# Sheet_SchDoc_2022-03-31.net
KiCad netlist of a schematic drawn in Altium Designer
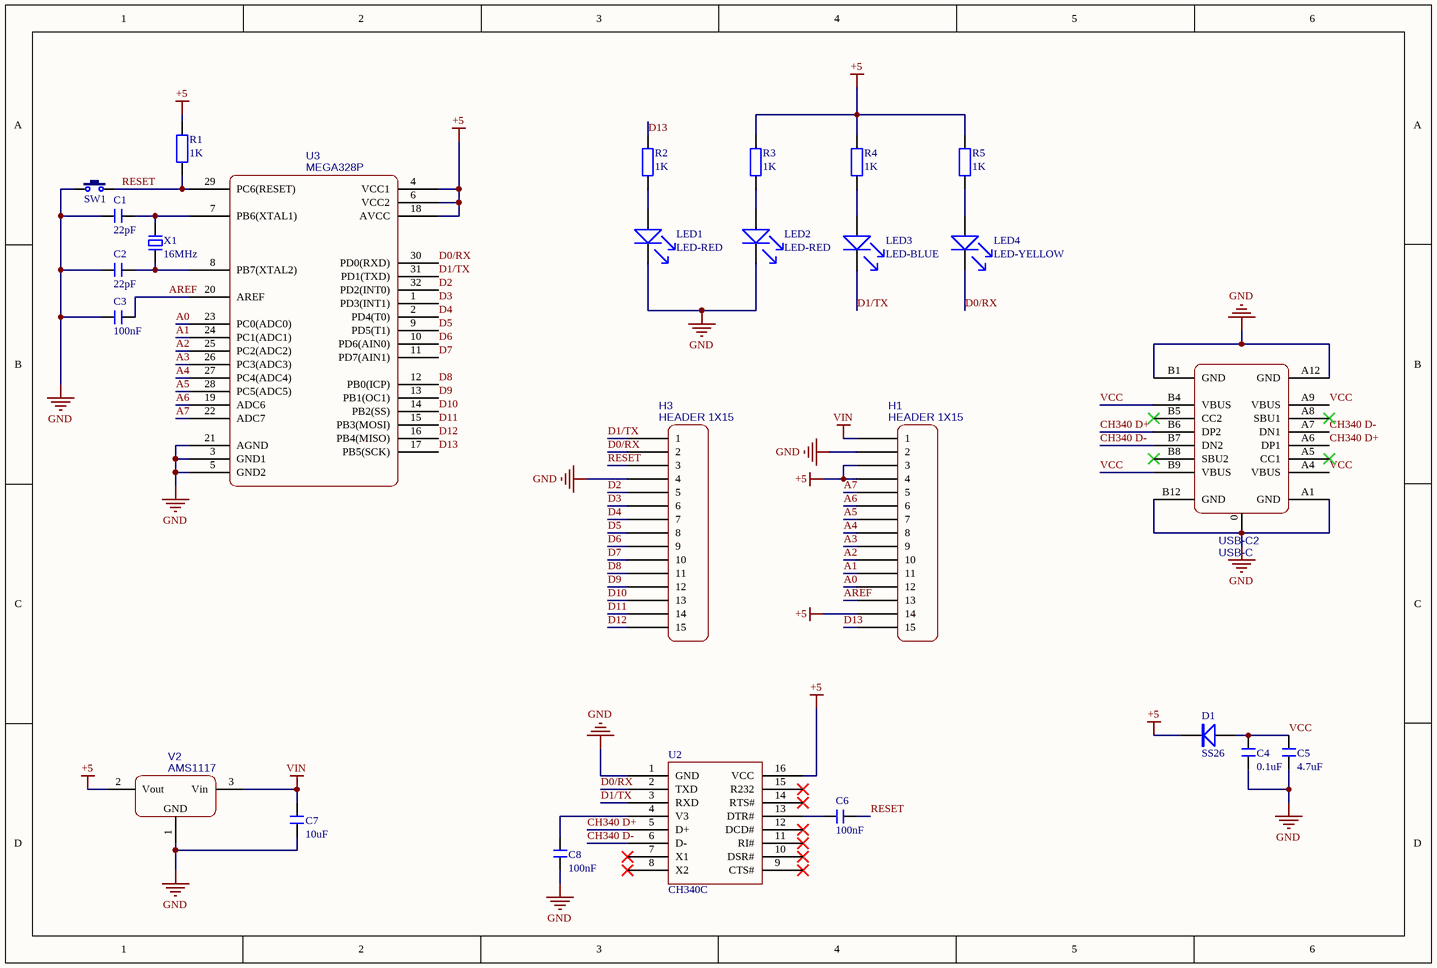
[diagram p0: Sheet.SchDoc_2022-03-31.schdoc]

(export (version "E")
  (design (tool "Eeschema 10.0.6"))
  (components
    (comp (ref "C1") (value "22pF") (libsource (lib "altium-import") (part "root_0_22pF_")))
    (comp (ref "C2") (value "22pF") (libsource (lib "altium-import") (part "root_0_22pF_")))
    (comp (ref "C3") (value "100nF") (libsource (lib "altium-import") (part "root_0_100nF_")))
    (comp (ref "C4") (value "0.1uF") (libsource (lib "altium-import") (part "root_1_0.1uF_")))
    (comp (ref "C5") (value "4.7uF") (libsource (lib "altium-import") (part "root_1_4.7uF_")))
    (comp (ref "C6") (value "100nF") (libsource (lib "") (part "root_0_100nF__1")))
    (comp (ref "C7") (value "10uF") (libsource (lib "altium-import") (part "root_1_10uF_")))
    (comp (ref "C8") (value "100nF") (libsource (lib "altium-import") (part "root_1_100nF_")))
    (comp (ref "D1") (value "SS26") (libsource (lib "altium-import") (part "root_2_SS26_")))
    (comp (ref "H1")
      (value "HEADER 1X15")
      (fields (field (name "CONTRIBUTOR") "Aknice"))
      (libsource (lib "altium-import") (part "root_0_HEADER 1X15_"))
    )
    (comp (ref "H3")
      (value "HEADER 1X15")
      (fields (field (name "CONTRIBUTOR") "Aknice"))
      (libsource (lib "altium-import") (part "root_0_HEADER 1X15_"))
    )
    (comp (ref "LED1") (value "LED-RED") (libsource (lib "altium-import") (part "root_3_LED-RED_")))
    (comp (ref "LED2") (value "LED-RED") (libsource (lib "altium-import") (part "root_3_LED-RED_")))
    (comp (ref "LED3") (value "LED-BLUE") (libsource (lib "altium-import") (part "root_3_LED-BLUE_")))
    (comp (ref "LED4") (value "LED-YELLOW") (libsource (lib "altium-import") (part "root_3_LED-YELLOW_")))
    (comp (ref "R1") (value "1K") (libsource (lib "altium-import") (part "root_1_1K_")))
    (comp (ref "R2") (value "1K") (libsource (lib "altium-import") (part "root_1_1K_")))
    (comp (ref "R3") (value "1K") (libsource (lib "altium-import") (part "root_1_1K_")))
    (comp (ref "R4") (value "1K") (libsource (lib "altium-import") (part "root_1_1K_")))
    (comp (ref "R5") (value "1K") (libsource (lib "altium-import") (part "root_1_1K_")))
    (comp (ref "SW1") (value "3x6x5") (libsource (lib "altium-import") (part "root_0_3x6x5_")))
    (comp (ref "U2") (value "CH340C") (libsource (lib "altium-import") (part "root_0_CH340C_")))
    (comp (ref "U3")
      (value "MEGA328P")
      (fields (field (name "CONTRIBUTOR") "Aknice"))
      (libsource (lib "altium-import") (part "root_0_MEGA328P_"))
    )
    (comp (ref "USB-C2")
      (value "USB-C")
      (fields (field (name "CONTRIBUTOR") "Aknice"))
      (libsource (lib "altium-import") (part "root_0_USB-C_"))
    )
    (comp (ref "V2")
      (value "AMS1117")
      (fields (field (name "CONTRIBUTOR") "Aknice"))
      (libsource (lib "altium-import") (part "root_0_AMS1117_"))
    )
    (comp (ref "X1") (value "16MHz") (libsource (lib "altium-import") (part "root_1_16MHz_")))
  )
  (nets
    (net (code "1") (name "+5") (class "Default")
      (node (ref "D1") (pin "2") (pinfunction "K_2") (pintype "passive"))
      (node (ref "H1") (pin "14") (pinfunction "14_14") (pintype "passive"))
      (node (ref "H1") (pin "3") (pinfunction "3_3") (pintype "passive"))
      (node (ref "H1") (pin "4") (pinfunction "4_4") (pintype "passive"))
      (node (ref "R1") (pin "2") (pinfunction "2_2") (pintype "passive"))
      (node (ref "R3") (pin "2") (pinfunction "2_2") (pintype "passive"))
      (node (ref "R4") (pin "2") (pinfunction "2_2") (pintype "passive"))
      (node (ref "R5") (pin "2") (pinfunction "2_2") (pintype "passive"))
      (node (ref "U2") (pin "16") (pinfunction "VCC_16") (pintype "passive"))
      (node (ref "U3") (pin "18") (pinfunction "AVCC_18") (pintype "passive"))
      (node (ref "U3") (pin "4") (pinfunction "VCC1_4") (pintype "passive"))
      (node (ref "U3") (pin "6") (pinfunction "VCC2_6") (pintype "passive"))
      (node (ref "V2") (pin "2") (pinfunction "Vout_2") (pintype "passive"))
    )
    (net (code "2") (name "/A0") (class "Default")
      (node (ref "H1") (pin "12") (pinfunction "12_12") (pintype "passive"))
      (node (ref "U3") (pin "23") (pinfunction "PC0(ADC0)_23") (pintype "passive"))
    )
    (net (code "3") (name "/A1") (class "Default")
      (node (ref "H1") (pin "11") (pinfunction "11_11") (pintype "passive"))
      (node (ref "U3") (pin "24") (pinfunction "PC1(ADC1)_24") (pintype "passive"))
    )
    (net (code "4") (name "/A2") (class "Default")
      (node (ref "H1") (pin "10") (pinfunction "10_10") (pintype "passive"))
      (node (ref "U3") (pin "25") (pinfunction "PC2(ADC2)_25") (pintype "passive"))
    )
    (net (code "5") (name "/A3") (class "Default")
      (node (ref "H1") (pin "9") (pinfunction "9_9") (pintype "passive"))
      (node (ref "U3") (pin "26") (pinfunction "PC3(ADC3)_26") (pintype "passive"))
    )
    (net (code "6") (name "/A4") (class "Default")
      (node (ref "H1") (pin "8") (pinfunction "8_8") (pintype "passive"))
      (node (ref "U3") (pin "27") (pinfunction "PC4(ADC4)_27") (pintype "passive"))
    )
    (net (code "7") (name "/A5") (class "Default")
      (node (ref "H1") (pin "7") (pinfunction "7_7") (pintype "passive"))
      (node (ref "U3") (pin "28") (pinfunction "PC5(ADC5)_28") (pintype "passive"))
    )
    (net (code "8") (name "/A6") (class "Default")
      (node (ref "H1") (pin "6") (pinfunction "6_6") (pintype "passive"))
      (node (ref "U3") (pin "19") (pinfunction "ADC6_19") (pintype "passive"))
    )
    (net (code "9") (name "/A7") (class "Default")
      (node (ref "H1") (pin "5") (pinfunction "5_5") (pintype "passive"))
      (node (ref "U3") (pin "22") (pinfunction "ADC7_22") (pintype "passive"))
    )
    (net (code "10") (name "/AREF") (class "Default")
      (node (ref "C3") (pin "2") (pinfunction "2_2") (pintype "passive"))
      (node (ref "H1") (pin "13") (pinfunction "13_13") (pintype "passive"))
      (node (ref "U3") (pin "20") (pinfunction "AREF_20") (pintype "passive"))
    )
    (net (code "11") (name "/CH340 D+") (class "Default")
      (node (ref "U2") (pin "5") (pinfunction "D+_5") (pintype "passive"))
      (node (ref "USB-C2") (pin "A6") (pinfunction "DP1_A6") (pintype "passive"))
      (node (ref "USB-C2") (pin "B6") (pinfunction "DP2_B6") (pintype "passive"))
    )
    (net (code "12") (name "/CH340 D-") (class "Default")
      (node (ref "U2") (pin "6") (pinfunction "D-_6") (pintype "passive"))
      (node (ref "USB-C2") (pin "A7") (pinfunction "DN1_A7") (pintype "passive"))
      (node (ref "USB-C2") (pin "B7") (pinfunction "DN2_B7") (pintype "passive"))
    )
    (net (code "13") (name "/D0{slash}RX") (class "Default")
      (node (ref "H3") (pin "2") (pinfunction "2_2") (pintype "passive"))
      (node (ref "LED4") (pin "2") (pinfunction "2_2") (pintype "passive"))
      (node (ref "U2") (pin "2") (pinfunction "TXD_2") (pintype "passive"))
      (node (ref "U3") (pin "30") (pinfunction "PD0(RXD)_30") (pintype "passive"))
    )
    (net (code "14") (name "/D1{slash}TX") (class "Default")
      (node (ref "H3") (pin "1") (pinfunction "1_1") (pintype "passive"))
      (node (ref "LED3") (pin "2") (pinfunction "2_2") (pintype "passive"))
      (node (ref "U2") (pin "3") (pinfunction "RXD_3") (pintype "passive"))
      (node (ref "U3") (pin "31") (pinfunction "PD1(TXD)_31") (pintype "passive"))
    )
    (net (code "15") (name "/D2") (class "Default")
      (node (ref "H3") (pin "5") (pinfunction "5_5") (pintype "passive"))
      (node (ref "U3") (pin "32") (pinfunction "PD2(INT0)_32") (pintype "passive"))
    )
    (net (code "16") (name "/D3") (class "Default")
      (node (ref "H3") (pin "6") (pinfunction "6_6") (pintype "passive"))
      (node (ref "U3") (pin "1") (pinfunction "PD3(INT1)_1") (pintype "passive"))
    )
    (net (code "17") (name "/D4") (class "Default")
      (node (ref "H3") (pin "7") (pinfunction "7_7") (pintype "passive"))
      (node (ref "U3") (pin "2") (pinfunction "PD4(T0)_2") (pintype "passive"))
    )
    (net (code "18") (name "/D5") (class "Default")
      (node (ref "H3") (pin "8") (pinfunction "8_8") (pintype "passive"))
      (node (ref "U3") (pin "9") (pinfunction "PD5(T1)_9") (pintype "passive"))
    )
    (net (code "19") (name "/D6") (class "Default")
      (node (ref "H3") (pin "9") (pinfunction "9_9") (pintype "passive"))
      (node (ref "U3") (pin "10") (pinfunction "PD6(AIN0)_10") (pintype "passive"))
    )
    (net (code "20") (name "/D7") (class "Default")
      (node (ref "H3") (pin "10") (pinfunction "10_10") (pintype "passive"))
      (node (ref "U3") (pin "11") (pinfunction "PD7(AIN1)_11") (pintype "passive"))
    )
    (net (code "21") (name "/D8") (class "Default")
      (node (ref "H3") (pin "11") (pinfunction "11_11") (pintype "passive"))
      (node (ref "U3") (pin "12") (pinfunction "PB0(ICP)_12") (pintype "passive"))
    )
    (net (code "22") (name "/D9") (class "Default")
      (node (ref "H3") (pin "12") (pinfunction "12_12") (pintype "passive"))
      (node (ref "U3") (pin "13") (pinfunction "PB1(OC1)_13") (pintype "passive"))
    )
    (net (code "23") (name "/D10") (class "Default")
      (node (ref "H3") (pin "13") (pinfunction "13_13") (pintype "passive"))
      (node (ref "U3") (pin "14") (pinfunction "PB2(SS)_14") (pintype "passive"))
    )
    (net (code "24") (name "/D11") (class "Default")
      (node (ref "H3") (pin "14") (pinfunction "14_14") (pintype "passive"))
      (node (ref "U3") (pin "15") (pinfunction "PB3(MOSI)_15") (pintype "passive"))
    )
    (net (code "25") (name "/D12") (class "Default")
      (node (ref "H3") (pin "15") (pinfunction "15_15") (pintype "passive"))
      (node (ref "U3") (pin "16") (pinfunction "PB4(MISO)_16") (pintype "passive"))
    )
    (net (code "26") (name "/D13") (class "Default")
      (node (ref "H1") (pin "15") (pinfunction "15_15") (pintype "passive"))
      (node (ref "R2") (pin "2") (pinfunction "2_2") (pintype "passive"))
      (node (ref "U3") (pin "17") (pinfunction "PB5(SCK)_17") (pintype "passive"))
    )
    (net (code "27") (name "/RESET") (class "Default")
      (node (ref "C6") (pin "1") (pinfunction "1_1") (pintype "passive"))
      (node (ref "H3") (pin "3") (pinfunction "3_3") (pintype "passive"))
      (node (ref "R1") (pin "1") (pinfunction "1_1") (pintype "passive"))
      (node (ref "SW1") (pin "2") (pinfunction "2_2") (pintype "passive"))
      (node (ref "U3") (pin "29") (pinfunction "PC6(RESET)_29") (pintype "passive"))
    )
    (net (code "28") (name "/VCC") (class "Default")
      (node (ref "C4") (pin "2") (pinfunction "2_2") (pintype "passive"))
      (node (ref "C5") (pin "2") (pinfunction "2_2") (pintype "passive"))
      (node (ref "D1") (pin "1") (pinfunction "A_1") (pintype "passive"))
      (node (ref "USB-C2") (pin "A4") (pinfunction "VBUS_A4") (pintype "passive"))
      (node (ref "USB-C2") (pin "A9") (pinfunction "VBUS_A9") (pintype "passive"))
      (node (ref "USB-C2") (pin "B4") (pinfunction "VBUS_B4") (pintype "passive"))
      (node (ref "USB-C2") (pin "B9") (pinfunction "VBUS_B9") (pintype "passive"))
    )
    (net (code "29") (name "GND") (class "Default")
      (node (ref "C1") (pin "1") (pinfunction "1_1") (pintype "passive"))
      (node (ref "C2") (pin "1") (pinfunction "1_1") (pintype "passive"))
      (node (ref "C3") (pin "1") (pinfunction "1_1") (pintype "passive"))
      (node (ref "C4") (pin "1") (pinfunction "1_1") (pintype "passive"))
      (node (ref "C5") (pin "1") (pinfunction "1_1") (pintype "passive"))
      (node (ref "C7") (pin "1") (pinfunction "1_1") (pintype "passive"))
      (node (ref "C8") (pin "1") (pinfunction "1_1") (pintype "passive"))
      (node (ref "H1") (pin "2") (pinfunction "2_2") (pintype "passive"))
      (node (ref "H3") (pin "4") (pinfunction "4_4") (pintype "passive"))
      (node (ref "LED1") (pin "2") (pinfunction "2_2") (pintype "passive"))
      (node (ref "LED2") (pin "2") (pinfunction "2_2") (pintype "passive"))
      (node (ref "SW1") (pin "1") (pinfunction "1_1") (pintype "passive"))
      (node (ref "U2") (pin "1") (pinfunction "GND_1") (pintype "passive"))
      (node (ref "U3") (pin "21") (pinfunction "AGND_21") (pintype "passive"))
      (node (ref "U3") (pin "3") (pinfunction "GND1_3") (pintype "passive"))
      (node (ref "U3") (pin "5") (pinfunction "GND2_5") (pintype "passive"))
      (node (ref "USB-C2") (pin "A1") (pinfunction "GND_A1") (pintype "passive"))
      (node (ref "USB-C2") (pin "A12") (pinfunction "GND_A12") (pintype "passive"))
      (node (ref "USB-C2") (pin "B1") (pinfunction "GND_B1") (pintype "passive"))
      (node (ref "USB-C2") (pin "B12") (pinfunction "GND_B12") (pintype "passive"))
      (node (ref "V2") (pin "1") (pinfunction "GND_1") (pintype "passive"))
    )
    (net (code "30") (name "Net-(LED1-Pad1)") (class "Default")
      (node (ref "LED1") (pin "1") (pinfunction "1_1") (pintype "passive"))
      (node (ref "R2") (pin "1") (pinfunction "1_1") (pintype "passive"))
    )
    (net (code "31") (name "Net-(LED2-Pad1)") (class "Default")
      (node (ref "LED2") (pin "1") (pinfunction "1_1") (pintype "passive"))
      (node (ref "R3") (pin "1") (pinfunction "1_1") (pintype "passive"))
    )
    (net (code "32") (name "Net-(LED3-Pad1)") (class "Default")
      (node (ref "LED3") (pin "1") (pinfunction "1_1") (pintype "passive"))
      (node (ref "R4") (pin "1") (pinfunction "1_1") (pintype "passive"))
    )
    (net (code "33") (name "Net-(LED4-Pad1)") (class "Default")
      (node (ref "LED4") (pin "1") (pinfunction "1_1") (pintype "passive"))
      (node (ref "R5") (pin "1") (pinfunction "1_1") (pintype "passive"))
    )
    (net (code "34") (name "Net-(U2-DTR#)") (class "Default")
      (node (ref "C6") (pin "2") (pinfunction "2_2") (pintype "passive"))
      (node (ref "U2") (pin "13") (pinfunction "DTR#_13") (pintype "passive"))
    )
    (net (code "35") (name "Net-(U2-V3)") (class "Default")
      (node (ref "C8") (pin "2") (pinfunction "2_2") (pintype "passive"))
      (node (ref "U2") (pin "4") (pinfunction "V3_4") (pintype "passive"))
    )
    (net (code "36") (name "Net-(U3-PB6(XTAL1))") (class "Default")
      (node (ref "C1") (pin "2") (pinfunction "2_2") (pintype "passive"))
      (node (ref "U3") (pin "7") (pinfunction "PB6(XTAL1)_7") (pintype "passive"))
      (node (ref "X1") (pin "2") (pinfunction "2_2") (pintype "passive"))
    )
    (net (code "37") (name "Net-(U3-PB7(XTAL2))") (class "Default")
      (node (ref "C2") (pin "2") (pinfunction "2_2") (pintype "passive"))
      (node (ref "U3") (pin "8") (pinfunction "PB7(XTAL2)_8") (pintype "passive"))
      (node (ref "X1") (pin "1") (pinfunction "1_1") (pintype "passive"))
    )
    (net (code "38") (name "VIN") (class "Default")
      (node (ref "C7") (pin "2") (pinfunction "2_2") (pintype "passive"))
      (node (ref "H1") (pin "1") (pinfunction "1_1") (pintype "passive"))
      (node (ref "V2") (pin "3") (pinfunction "Vin_3") (pintype "passive"))
    )
    (net (code "39") (name "unconnected-(U2-CTS#-Pad9)") (class "Default")
      (node (ref "U2") (pin "9") (pinfunction "CTS#_9") (pintype "passive+no_connect"))
    )
    (net (code "40") (name "unconnected-(U2-DCD#-Pad12)") (class "Default")
      (node (ref "U2") (pin "12") (pinfunction "DCD#_12") (pintype "passive+no_connect"))
    )
    (net (code "41") (name "unconnected-(U2-DSR#-Pad10)") (class "Default")
      (node (ref "U2") (pin "10") (pinfunction "DSR#_10") (pintype "passive+no_connect"))
    )
    (net (code "42") (name "unconnected-(U2-R232-Pad15)") (class "Default")
      (node (ref "U2") (pin "15") (pinfunction "R232_15") (pintype "passive+no_connect"))
    )
    (net (code "43") (name "unconnected-(U2-RI#-Pad11)") (class "Default")
      (node (ref "U2") (pin "11") (pinfunction "RI#_11") (pintype "passive+no_connect"))
    )
    (net (code "44") (name "unconnected-(U2-RTS#-Pad14)") (class "Default")
      (node (ref "U2") (pin "14") (pinfunction "RTS#_14") (pintype "passive+no_connect"))
    )
    (net (code "45") (name "unconnected-(U2-X1-Pad7)") (class "Default")
      (node (ref "U2") (pin "7") (pinfunction "X1_7") (pintype "passive+no_connect"))
    )
    (net (code "46") (name "unconnected-(U2-X2-Pad8)") (class "Default")
      (node (ref "U2") (pin "8") (pinfunction "X2_8") (pintype "passive+no_connect"))
    )
    (net (code "47") (name "unconnected-(USB-C2-CC1-PadA5)") (class "Default")
      (node (ref "USB-C2") (pin "A5") (pinfunction "CC1_A5") (pintype "passive+no_connect"))
    )
    (net (code "48") (name "unconnected-(USB-C2-CC2-PadB5)") (class "Default")
      (node (ref "USB-C2") (pin "B5") (pinfunction "CC2_B5") (pintype "passive+no_connect"))
    )
    (net (code "49") (name "unconnected-(USB-C2-Pad0)") (class "Default")
      (node (ref "USB-C2") (pin "0") (pinfunction "0_0") (pintype "passive"))
    )
    (net (code "50") (name "unconnected-(USB-C2-SBU1-PadA8)") (class "Default")
      (node (ref "USB-C2") (pin "A8") (pinfunction "SBU1_A8") (pintype "passive+no_connect"))
    )
    (net (code "51") (name "unconnected-(USB-C2-SBU2-PadB8)") (class "Default")
      (node (ref "USB-C2") (pin "B8") (pinfunction "SBU2_B8") (pintype "passive+no_connect"))
    )
  )
)
